# USB_Serial.net
KiCad netlist of a schematic drawn in Altium Designer
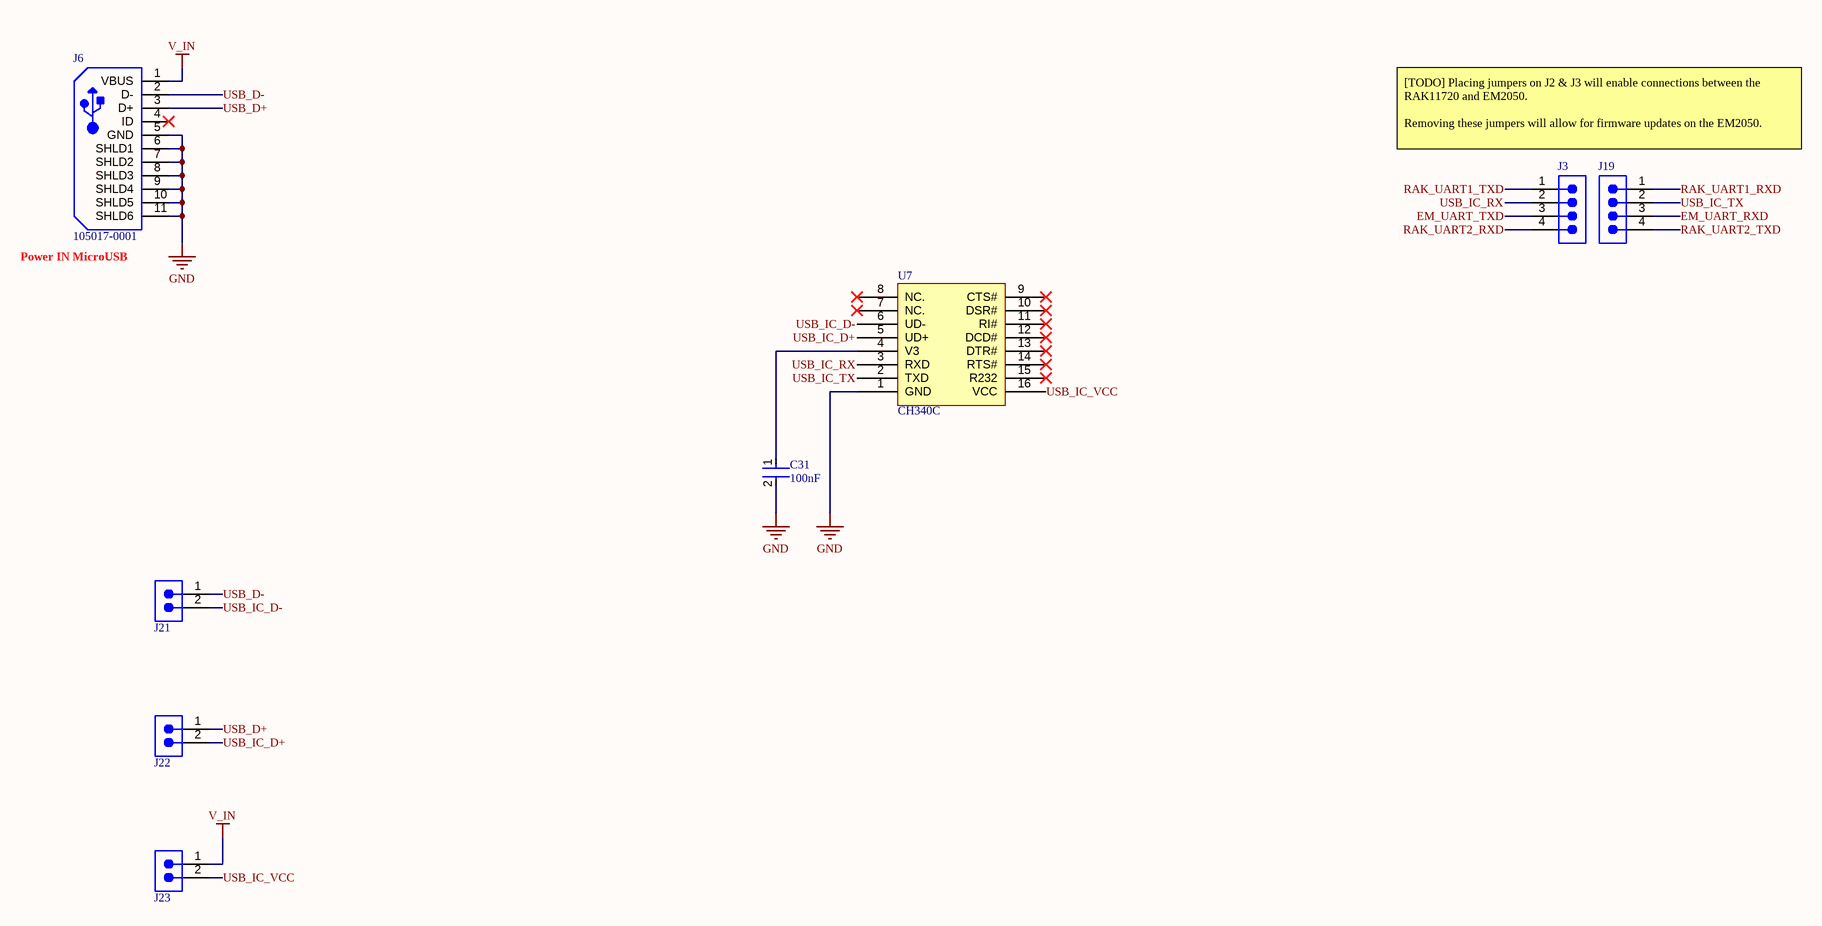
[diagram p0: USB_Serial.SchDoc]

(export (version "E")
  (design (tool "Eeschema 10.0.6"))
  (components
    (comp (ref "C31")
      (value "0402ZD104KAT2A")
      (footprint "FP-0402-L_1_0_1-W_0_5_0_1-IPC_C")
      (description "General Purpose Ceramic Capacitor, 0402, 100nF, 10%, X5R, 15%, 10V")
      (fields
        (field (name "VOLTAGE") "10V")
        (field (name "TOLERANCE") "10%")
        (field (name "CAPACITANCE") "100nF")
      )
      (libsource (lib "Altium Content Vault") (part "b4654b650e69147ec39a6b967a45e02"))
    )
    (comp (ref "J3")
      (value "61300411121")
      (footprint "61300411121")
      (libsource (lib "Altium Content Vault") (part "Header_Male_1R_04P"))
    )
    (comp (ref "J6")
      (value "105017-0001")
      (footprint "USB-MICRO-B_V")
      (fields (field (name "MANUFACTURER") "Molex"))
      (libsource (lib "Altium Content Vault") (part "USB-5-6SHLD"))
    )
    (comp (ref "J19")
      (value "61300411121")
      (footprint "61300411121")
      (libsource (lib "Altium Content Vault") (part "Header_Male_1R_04P"))
    )
    (comp (ref "J21")
      (value "61300211121")
      (footprint "61300211121")
      (libsource (lib "Altium Content Vault") (part "Header_Male_1R_02P"))
    )
    (comp (ref "J22")
      (value "61300211121")
      (footprint "61300211121")
      (libsource (lib "Altium Content Vault") (part "Header_Male_1R_02P"))
    )
    (comp (ref "J23")
      (value "61300211121")
      (footprint "61300211121")
      (libsource (lib "Altium Content Vault") (part "Header_Male_1R_02P"))
    )
    (comp (ref "U7")
      (value "CH340C")
      (footprint "CH340C")
      (description "USB to Serial CH340 IC")
      (libsource (lib "RAK3172_RF_Generator") (part "CH340C"))
    )
  )
  (nets
    (net (code "1") (name "/EM_UART_RXD") (class "Default")
      (node (ref "J19") (pin "3") (pinfunction "3_3") (pintype "passive"))
    )
    (net (code "2") (name "/EM_UART_TXD") (class "Default")
      (node (ref "J3") (pin "3") (pinfunction "3_3") (pintype "passive"))
    )
    (net (code "3") (name "/RAK_UART1_RXD") (class "Default")
      (node (ref "J19") (pin "1") (pinfunction "1_1") (pintype "passive"))
    )
    (net (code "4") (name "/RAK_UART1_TXD") (class "Default")
      (node (ref "J3") (pin "1") (pinfunction "1_1") (pintype "passive"))
    )
    (net (code "5") (name "/RAK_UART2_RXD") (class "Default")
      (node (ref "J3") (pin "4") (pinfunction "4_4") (pintype "passive"))
    )
    (net (code "6") (name "/RAK_UART2_TXD") (class "Default")
      (node (ref "J19") (pin "4") (pinfunction "4_4") (pintype "passive"))
    )
    (net (code "7") (name "/USB_D+") (class "Default")
      (node (ref "J22") (pin "1") (pinfunction "1_1") (pintype "passive"))
      (node (ref "J6") (pin "3") (pinfunction "D+_3") (pintype "passive"))
    )
    (net (code "8") (name "/USB_D-") (class "Default")
      (node (ref "J21") (pin "1") (pinfunction "1_1") (pintype "passive"))
      (node (ref "J6") (pin "2") (pinfunction "D-_2") (pintype "passive"))
    )
    (net (code "9") (name "/USB_IC_D+") (class "Default")
      (node (ref "J22") (pin "2") (pinfunction "2_2") (pintype "passive"))
      (node (ref "U7") (pin "5") (pinfunction "UD+_5") (pintype "passive"))
    )
    (net (code "10") (name "/USB_IC_D-") (class "Default")
      (node (ref "J21") (pin "2") (pinfunction "2_2") (pintype "passive"))
      (node (ref "U7") (pin "6") (pinfunction "UD-_6") (pintype "passive"))
    )
    (net (code "11") (name "/USB_IC_RX") (class "Default")
      (node (ref "J3") (pin "2") (pinfunction "2_2") (pintype "passive"))
      (node (ref "U7") (pin "3") (pinfunction "RXD_3") (pintype "passive"))
    )
    (net (code "12") (name "/USB_IC_TX") (class "Default")
      (node (ref "J19") (pin "2") (pinfunction "2_2") (pintype "passive"))
      (node (ref "U7") (pin "2") (pinfunction "TXD_2") (pintype "passive"))
    )
    (net (code "13") (name "/USB_IC_VCC") (class "Default")
      (node (ref "J23") (pin "2") (pinfunction "2_2") (pintype "passive"))
      (node (ref "U7") (pin "16") (pinfunction "VCC_16") (pintype "passive"))
    )
    (net (code "14") (name "GND") (class "Default")
      (node (ref "C31") (pin "2") (pinfunction "2_2") (pintype "passive"))
      (node (ref "J6") (pin "10") (pinfunction "SHLD5_10") (pintype "passive"))
      (node (ref "J6") (pin "11") (pinfunction "SHLD6_11") (pintype "passive"))
      (node (ref "J6") (pin "5") (pinfunction "GND_5") (pintype "passive"))
      (node (ref "J6") (pin "6") (pinfunction "SHLD1_6") (pintype "passive"))
      (node (ref "J6") (pin "7") (pinfunction "SHLD2_7") (pintype "passive"))
      (node (ref "J6") (pin "8") (pinfunction "SHLD3_8") (pintype "passive"))
      (node (ref "J6") (pin "9") (pinfunction "SHLD4_9") (pintype "passive"))
      (node (ref "U7") (pin "1") (pinfunction "GND_1") (pintype "passive"))
    )
    (net (code "15") (name "Net-(U7-V3)") (class "Default")
      (node (ref "C31") (pin "1") (pinfunction "1_1") (pintype "passive"))
      (node (ref "U7") (pin "4") (pinfunction "V3_4") (pintype "passive"))
    )
    (net (code "16") (name "V_IN") (class "Default")
      (node (ref "J23") (pin "1") (pinfunction "1_1") (pintype "passive"))
      (node (ref "J6") (pin "1") (pinfunction "VBUS_1") (pintype "passive"))
    )
    (net (code "17") (name "unconnected-(J6-ID-Pad4)") (class "Default")
      (node (ref "J6") (pin "4") (pinfunction "ID_4") (pintype "passive+no_connect"))
    )
    (net (code "18") (name "unconnected-(U7-CTS#-Pad9)") (class "Default")
      (node (ref "U7") (pin "9") (pinfunction "CTS#_9") (pintype "passive+no_connect"))
    )
    (net (code "19") (name "unconnected-(U7-DCD#-Pad12)") (class "Default")
      (node (ref "U7") (pin "12") (pinfunction "DCD#_12") (pintype "passive+no_connect"))
    )
    (net (code "20") (name "unconnected-(U7-DSR#-Pad10)") (class "Default")
      (node (ref "U7") (pin "10") (pinfunction "DSR#_10") (pintype "passive+no_connect"))
    )
    (net (code "21") (name "unconnected-(U7-DTR#-Pad13)") (class "Default")
      (node (ref "U7") (pin "13") (pinfunction "DTR#_13") (pintype "passive+no_connect"))
    )
    (net (code "22") (name "unconnected-(U7-NC.-Pad7)") (class "Default")
      (node (ref "U7") (pin "7") (pinfunction "NC._7") (pintype "passive+no_connect"))
    )
    (net (code "23") (name "unconnected-(U7-NC.-Pad8)") (class "Default")
      (node (ref "U7") (pin "8") (pinfunction "NC._8") (pintype "passive+no_connect"))
    )
    (net (code "24") (name "unconnected-(U7-R232-Pad15)") (class "Default")
      (node (ref "U7") (pin "15") (pinfunction "R232_15") (pintype "passive+no_connect"))
    )
    (net (code "25") (name "unconnected-(U7-RI#-Pad11)") (class "Default")
      (node (ref "U7") (pin "11") (pinfunction "RI#_11") (pintype "passive+no_connect"))
    )
    (net (code "26") (name "unconnected-(U7-RTS#-Pad14)") (class "Default")
      (node (ref "U7") (pin "14") (pinfunction "RTS#_14") (pintype "passive+no_connect"))
    )
  )
)
